# eps_bt1.net
KiCad netlist of a schematic drawn in Altium Designer
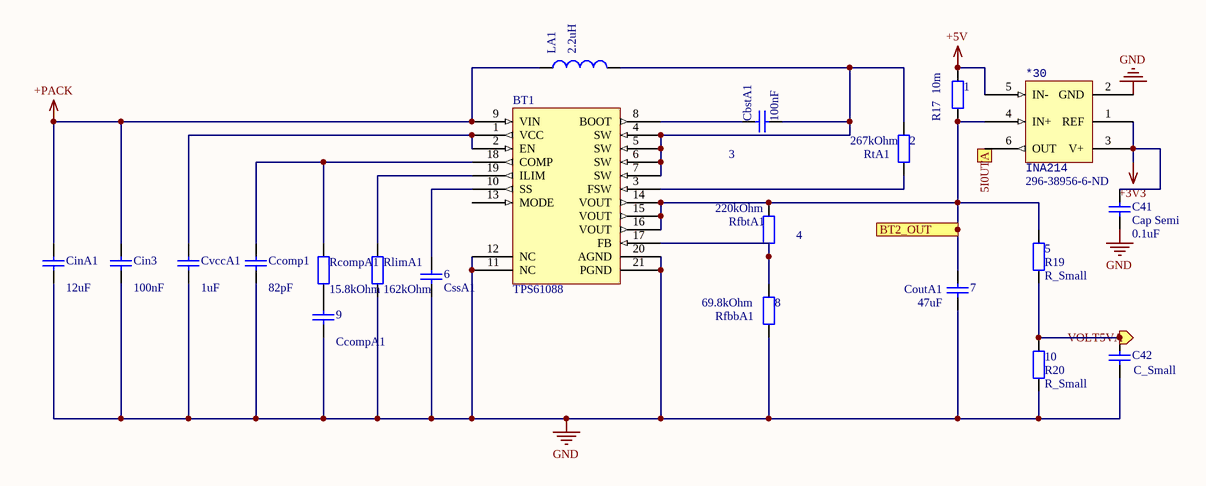
[diagram p0: eps_bt1.SchDoc]

(export (version "E")
  (design (tool "Eeschema 10.0.6"))
  (components
    (comp (ref "*30")
      (value "INA214")
      (footprint "SOT65P210X110-6N")
      (description "Current monitor")
      (fields (field (name "SUPPLIER PART NUMBER 1") "296-38956-6-ND"))
      (libsource (lib "heron-general") (part "INA214"))
    )
    (comp (ref "1")
      (value "R17")
      (footprint "1608[0603]")
      (description "Resistor")
      (fields (field (name "ALTIUM_VALUE") "10m") (field (name "PUBLISHER") "Altium Limited"))
      (libsource (lib "") (part "Res2_1"))
    )
    (comp (ref "2")
      (value "RtA1")
      (footprint "1608[0603]")
      (description "Resistor")
      (fields (field (name "ALTIUM_VALUE") "267kOhm") (field (name "PUBLISHER") "Altium Limited"))
      (libsource (lib "Miscellaneous Devices") (part "Res2"))
    )
    (comp (ref "3")
      (value "CbstA1")
      (footprint "1608[0603]")
      (description "Capacitor")
      (fields (field (name "ALTIUM_VALUE") "100nF") (field (name "PUBLISHER") "Altium Limited"))
      (libsource (lib "Miscellaneous Devices") (part "Cap"))
    )
    (comp (ref "4")
      (value "RfbtA1")
      (footprint "1608[0603]")
      (description "Resistor")
      (fields (field (name "ALTIUM_VALUE") "220kOhm") (field (name "PUBLISHER") "Altium Limited"))
      (libsource (lib "") (part "Res2_1"))
    )
    (comp (ref "5")
      (value "R19")
      (footprint "1608[0603]")
      (description "Resistor")
      (fields (field (name "ALTIUM_VALUE") "R_Small") (field (name "PUBLISHER") "Altium Limited"))
      (libsource (lib "") (part "Res2_1"))
    )
    (comp (ref "6")
      (value "CssA1")
      (footprint "1608[0603]")
      (description "Capacitor")
      (fields (field (name "PUBLISHER") "Altium Limited"))
      (libsource (lib "Miscellaneous Devices") (part "Cap"))
    )
    (comp (ref "7")
      (value "CoutA1")
      (footprint "1608[0603]")
      (description "Capacitor")
      (fields (field (name "ALTIUM_VALUE") "47uF") (field (name "PUBLISHER") "Altium Limited"))
      (libsource (lib "Miscellaneous Devices") (part "Cap"))
    )
    (comp (ref "8")
      (value "RfbbA1")
      (footprint "1608[0603]")
      (description "Resistor")
      (fields (field (name "ALTIUM_VALUE") "69.8kOhm") (field (name "PUBLISHER") "Altium Limited"))
      (libsource (lib "") (part "Res2_1"))
    )
    (comp (ref "9")
      (value "CcompA1")
      (footprint "1608[0603]")
      (description "Capacitor")
      (fields (field (name "PUBLISHER") "Altium Limited"))
      (libsource (lib "Miscellaneous Devices") (part "Cap"))
    )
    (comp (ref "10")
      (value "R20")
      (footprint "1608[0603]")
      (description "Resistor")
      (fields (field (name "ALTIUM_VALUE") "R_Small") (field (name "PUBLISHER") "Altium Limited"))
      (libsource (lib "") (part "Res2_1"))
    )
    (comp (ref "BT1")
      (value "TPS61088")
      (footprint "QFN50P450X350X100-21N")
      (description "Boost converter")
      (libsource (lib "heron-general") (part "TPS61088"))
    )
    (comp (ref "C41")
      (value "Cap Semi")
      (footprint "1608[0603]")
      (description "Capacitor (Semiconductor SIM Model)")
      (fields (field (name "ALTIUM_VALUE") "0.1uF") (field (name "PUBLISHER") "Altium Limited"))
      (libsource (lib "Miscellaneous Devices") (part "Cap Semi"))
    )
    (comp (ref "C42")
      (value "C_Small")
      (footprint "1608[0603]")
      (description "Capacitor")
      (fields (field (name "PUBLISHER") "Altium Limited"))
      (libsource (lib "Miscellaneous Devices") (part "Cap"))
    )
    (comp (ref "Ccomp1")
      (value "82pF")
      (footprint "1608[0603]")
      (description "Capacitor")
      (fields (field (name "PUBLISHER") "Altium Limited"))
      (libsource (lib "Miscellaneous Devices") (part "Cap"))
    )
    (comp (ref "Cin3")
      (value "100nF")
      (footprint "1608[0603]")
      (description "Capacitor")
      (fields (field (name "PUBLISHER") "Altium Limited"))
      (libsource (lib "Miscellaneous Devices") (part "Cap"))
    )
    (comp (ref "CinA1")
      (value "12uF")
      (footprint "1608[0603]")
      (description "Capacitor")
      (fields (field (name "PUBLISHER") "Altium Limited"))
      (libsource (lib "Miscellaneous Devices") (part "Cap"))
    )
    (comp (ref "CvccA1")
      (value "1uF")
      (footprint "1608[0603]")
      (description "Capacitor")
      (fields (field (name "PUBLISHER") "Altium Limited"))
      (libsource (lib "Miscellaneous Devices") (part "Cap"))
    )
    (comp (ref "LA1")
      (value "2.2uH")
      (footprint "1608[0603]")
      (description "Inductor")
      (fields (field (name "PUBLISHER") "Altium Limited"))
      (libsource (lib "Miscellaneous Devices") (part "Inductor"))
    )
    (comp (ref "RcompA1")
      (value "15.8kOhm")
      (footprint "1608[0603]")
      (description "Resistor")
      (fields (field (name "PUBLISHER") "Altium Limited"))
      (libsource (lib "") (part "Res2_1"))
    )
    (comp (ref "RlimA1")
      (value "162kOhm")
      (footprint "1608[0603]")
      (description "Resistor")
      (fields (field (name "PUBLISHER") "Altium Limited"))
      (libsource (lib "") (part "Res2_1"))
    )
  )
  (nets
    (net (code "1") (name "+3V3") (class "Default")
      (node (ref "*30") (pin "1") (pinfunction "REF_1") (pintype "passive"))
      (node (ref "*30") (pin "3") (pinfunction "V+_3") (pintype "power_in"))
      (node (ref "C41") (pin "2") (pinfunction "2_2") (pintype "passive"))
    )
    (net (code "2") (name "+5V") (class "Default")
      (node (ref "*30") (pin "5") (pinfunction "IN-_5") (pintype "input"))
      (node (ref "1") (pin "2") (pinfunction "2_2") (pintype "passive"))
    )
    (net (code "3") (name "+PACK") (class "Default")
      (node (ref "BT1") (pin "9") (pinfunction "VIN_9") (pintype "input"))
      (node (ref "Cin3") (pin "2") (pinfunction "2_2") (pintype "passive"))
      (node (ref "CinA1") (pin "2") (pinfunction "2_2") (pintype "passive"))
      (node (ref "LA1") (pin "1") (pinfunction "1_1") (pintype "passive"))
    )
    (net (code "4") (name "/5I0UTA") (class "Default")
      (node (ref "*30") (pin "6") (pinfunction "OUT_6") (pintype "output"))
    )
    (net (code "5") (name "/BT2_OUT") (class "Default")
      (node (ref "*30") (pin "4") (pinfunction "IN+_4") (pintype "input"))
      (node (ref "1") (pin "1") (pinfunction "1_1") (pintype "passive"))
      (node (ref "4") (pin "2") (pinfunction "2_2") (pintype "passive"))
      (node (ref "5") (pin "2") (pinfunction "2_2") (pintype "passive"))
      (node (ref "7") (pin "2") (pinfunction "2_2") (pintype "passive"))
      (node (ref "BT1") (pin "14") (pinfunction "VOUT_14") (pintype "output"))
      (node (ref "BT1") (pin "15") (pinfunction "VOUT_15") (pintype "output"))
      (node (ref "BT1") (pin "16") (pinfunction "VOUT_16") (pintype "output"))
    )
    (net (code "6") (name "/VOLT5VA") (class "Default")
      (node (ref "10") (pin "2") (pinfunction "2_2") (pintype "passive"))
      (node (ref "5") (pin "1") (pinfunction "1_1") (pintype "passive"))
      (node (ref "C42") (pin "1") (pinfunction "1_1") (pintype "passive"))
    )
    (net (code "7") (name "GND") (class "Default")
      (node (ref "*30") (pin "2") (pinfunction "GND_2") (pintype "power_in"))
      (node (ref "10") (pin "1") (pinfunction "1_1") (pintype "passive"))
      (node (ref "6") (pin "1") (pinfunction "1_1") (pintype "passive"))
      (node (ref "7") (pin "1") (pinfunction "1_1") (pintype "passive"))
      (node (ref "8") (pin "1") (pinfunction "1_1") (pintype "passive"))
      (node (ref "9") (pin "1") (pinfunction "1_1") (pintype "passive"))
      (node (ref "BT1") (pin "11") (pinfunction "NC_11") (pintype "passive"))
      (node (ref "BT1") (pin "12") (pinfunction "NC_12") (pintype "passive"))
      (node (ref "BT1") (pin "20") (pinfunction "AGND_20") (pintype "power_in"))
      (node (ref "BT1") (pin "21") (pinfunction "PGND_21") (pintype "power_in"))
      (node (ref "C41") (pin "1") (pinfunction "1_1") (pintype "passive"))
      (node (ref "C42") (pin "2") (pinfunction "2_2") (pintype "passive"))
      (node (ref "Ccomp1") (pin "1") (pinfunction "1_1") (pintype "passive"))
      (node (ref "Cin3") (pin "1") (pinfunction "1_1") (pintype "passive"))
      (node (ref "CinA1") (pin "1") (pinfunction "1_1") (pintype "passive"))
      (node (ref "CvccA1") (pin "1") (pinfunction "1_1") (pintype "passive"))
      (node (ref "RlimA1") (pin "1") (pinfunction "1_1") (pintype "passive"))
    )
    (net (code "8") (name "Net-(2-Pad1)") (class "Default")
      (node (ref "2") (pin "1") (pinfunction "1_1") (pintype "passive"))
      (node (ref "3") (pin "1") (pinfunction "1_1") (pintype "passive"))
      (node (ref "BT1") (pin "4") (pinfunction "SW_4") (pintype "input"))
      (node (ref "BT1") (pin "5") (pinfunction "SW_5") (pintype "input"))
      (node (ref "BT1") (pin "6") (pinfunction "SW_6") (pintype "input"))
      (node (ref "BT1") (pin "7") (pinfunction "SW_7") (pintype "input"))
      (node (ref "LA1") (pin "2") (pinfunction "2_2") (pintype "passive"))
    )
    (net (code "9") (name "Net-(9-Pad2)") (class "Default")
      (node (ref "9") (pin "2") (pinfunction "2_2") (pintype "passive"))
      (node (ref "RcompA1") (pin "1") (pinfunction "1_1") (pintype "passive"))
    )
    (net (code "10") (name "Net-(BT1-BOOT)") (class "Default")
      (node (ref "3") (pin "2") (pinfunction "2_2") (pintype "passive"))
      (node (ref "BT1") (pin "8") (pinfunction "BOOT_8") (pintype "output"))
    )
    (net (code "11") (name "Net-(BT1-COMP)") (class "Default")
      (node (ref "BT1") (pin "18") (pinfunction "COMP_18") (pintype "output"))
      (node (ref "Ccomp1") (pin "2") (pinfunction "2_2") (pintype "passive"))
      (node (ref "RcompA1") (pin "2") (pinfunction "2_2") (pintype "passive"))
    )
    (net (code "12") (name "Net-(BT1-EN)") (class "Default")
      (node (ref "BT1") (pin "1") (pinfunction "VCC_1") (pintype "output"))
      (node (ref "BT1") (pin "2") (pinfunction "EN_2") (pintype "input"))
      (node (ref "CvccA1") (pin "2") (pinfunction "2_2") (pintype "passive"))
    )
    (net (code "13") (name "Net-(BT1-FB)") (class "Default")
      (node (ref "4") (pin "1") (pinfunction "1_1") (pintype "passive"))
      (node (ref "8") (pin "2") (pinfunction "2_2") (pintype "passive"))
      (node (ref "BT1") (pin "17") (pinfunction "FB_17") (pintype "input"))
    )
    (net (code "14") (name "Net-(BT1-FSW)") (class "Default")
      (node (ref "2") (pin "2") (pinfunction "2_2") (pintype "passive"))
      (node (ref "BT1") (pin "3") (pinfunction "FSW_3") (pintype "input"))
    )
    (net (code "15") (name "Net-(BT1-ILIM)") (class "Default")
      (node (ref "BT1") (pin "19") (pinfunction "ILIM_19") (pintype "output"))
      (node (ref "RlimA1") (pin "2") (pinfunction "2_2") (pintype "passive"))
    )
    (net (code "16") (name "Net-(BT1-SS)") (class "Default")
      (node (ref "6") (pin "2") (pinfunction "2_2") (pintype "passive"))
      (node (ref "BT1") (pin "10") (pinfunction "SS_10") (pintype "output"))
    )
    (net (code "17") (name "unconnected-(BT1-MODE-Pad13)") (class "Default")
      (node (ref "BT1") (pin "13") (pinfunction "MODE_13") (pintype "input"))
    )
  )
)
